# MoodBadgeRev00.net
KiCad netlist of a schematic drawn in EAGLE
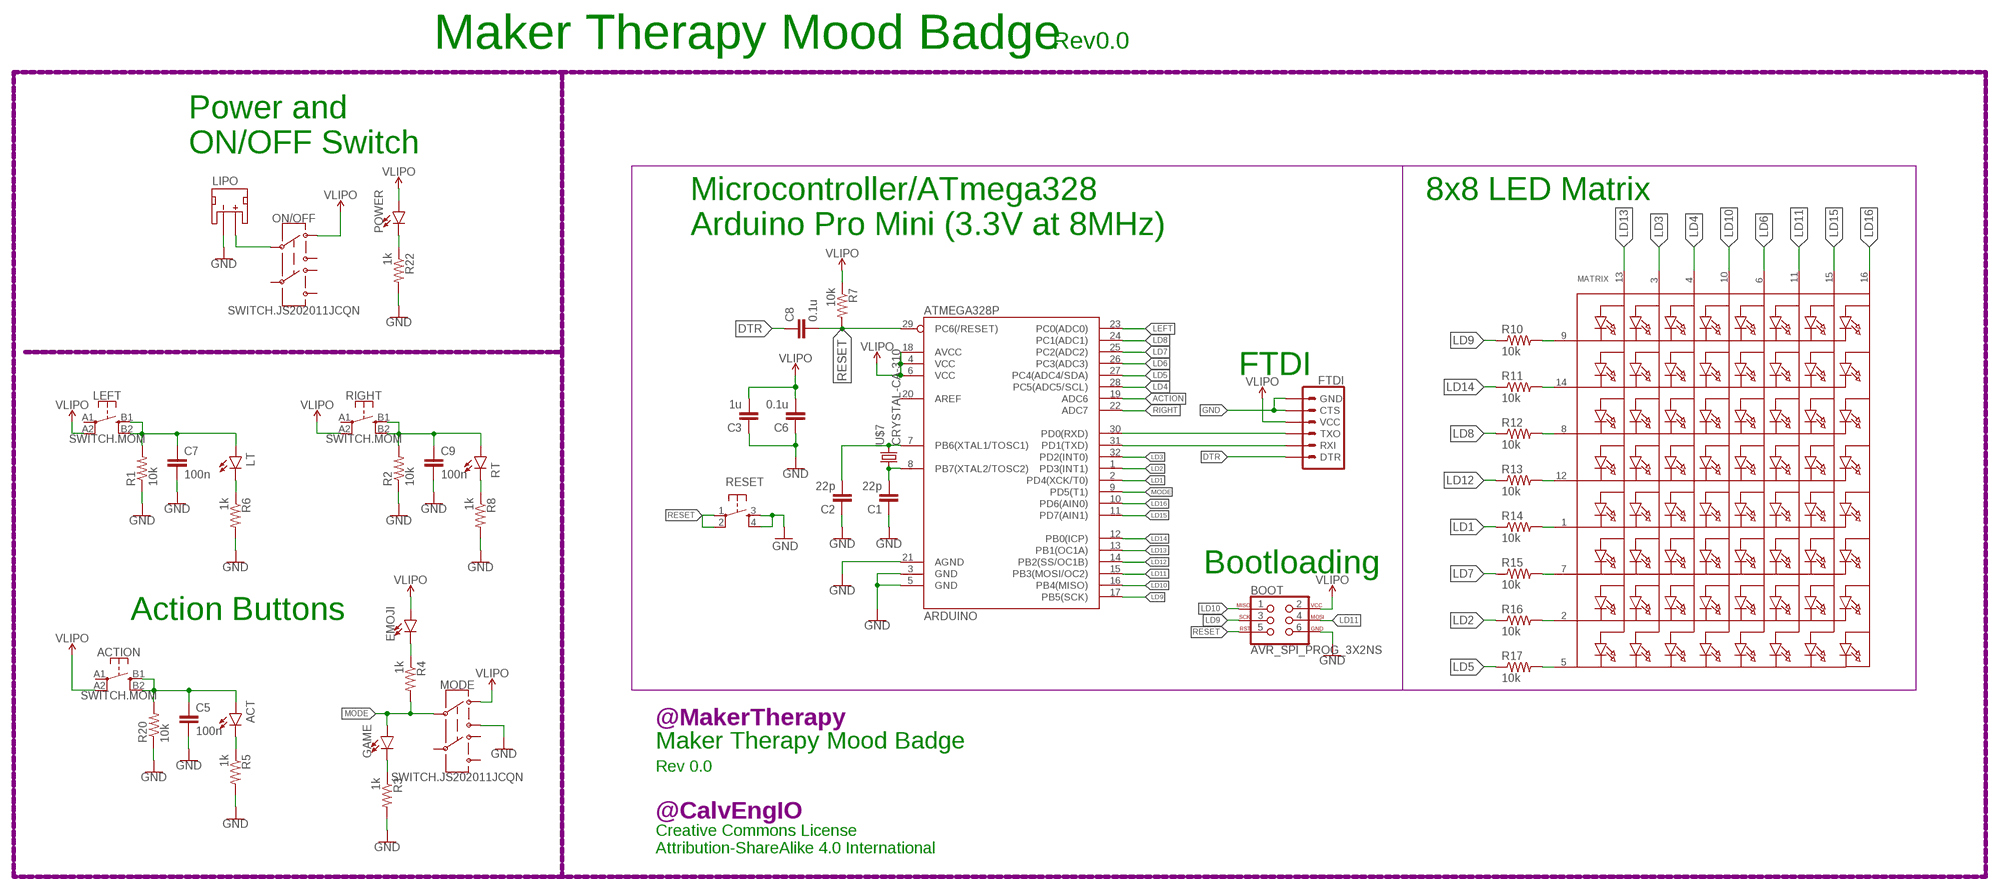
[diagram p0: schematic, sheet 1]

(export (version "E")
  (design (tool "Eeschema 10.0.6"))
  (components
    (comp (ref "ACT")
      (value "LED0603")
      (footprint "eagle-import:LED-0603")
      (libsource (lib "eagle-import") (part "LED0603"))
    )
    (comp (ref "ACTION")
      (value "SWITCH.MOM")
      (footprint "eagle-import:TACTILE_SWITCH_SMD_6.2MM_TALL")
      (libsource (lib "eagle-import") (part "SWITCH.MOM"))
    )
    (comp (ref "ARDUINO")
      (value "ATMEGA328P")
      (footprint "eagle-import:TQFP32-08")
      (libsource (lib "eagle-import") (part "ATMEGA328_SMT-OHMOD"))
    )
    (comp (ref "BOOT")
      (value "AVR_SPI_PROG_3X2NS")
      (footprint "eagle-import:2X3-NS")
      (libsource (lib "eagle-import") (part "AVR_SPI_PROG_3X2NS"))
    )
    (comp (ref "C1")
      (value "22p")
      (footprint "eagle-import:C0402")
      (libsource (lib "eagle-import") (part "CAPACITOR0402"))
    )
    (comp (ref "C2")
      (value "22p")
      (footprint "eagle-import:C0402")
      (libsource (lib "eagle-import") (part "CAPACITOR0402"))
    )
    (comp (ref "C3")
      (value "1u")
      (footprint "eagle-import:C0402")
      (libsource (lib "eagle-import") (part "CAPACITOR0402"))
    )
    (comp (ref "C5")
      (value "100n")
      (footprint "eagle-import:C0402")
      (libsource (lib "eagle-import") (part "CAPACITOR0402"))
    )
    (comp (ref "C6")
      (value "0.1u")
      (footprint "eagle-import:C0402")
      (libsource (lib "eagle-import") (part "CAPACITOR0402"))
    )
    (comp (ref "C7")
      (value "100n")
      (footprint "eagle-import:C0402")
      (libsource (lib "eagle-import") (part "CAPACITOR0402"))
    )
    (comp (ref "C8")
      (value "0.1u")
      (footprint "eagle-import:C0402")
      (libsource (lib "eagle-import") (part "C-EUC0402"))
    )
    (comp (ref "C9")
      (value "100n")
      (footprint "eagle-import:C0402")
      (libsource (lib "eagle-import") (part "CAPACITOR0402"))
    )
    (comp (ref "EMOJI")
      (value "LED0603")
      (footprint "eagle-import:LED-0603")
      (libsource (lib "eagle-import") (part "LED0603"))
    )
    (comp (ref "FTDI")
      (value "6_PIN_SERIAL_TARGETSILK")
      (footprint "eagle-import:6_PIN_SERIAL_TARGET_SIDE_W_SILK")
      (libsource (lib "eagle-import") (part "6_PIN_SERIAL_TARGETSILK"))
    )
    (comp (ref "GAME")
      (value "LED0603")
      (footprint "eagle-import:LED-0603")
      (libsource (lib "eagle-import") (part "LED0603"))
    )
    (comp (ref "LEFT")
      (value "SWITCH.MOM")
      (footprint "eagle-import:TACTILE_SWITCH_SMD_6.2MM_TALL")
      (libsource (lib "eagle-import") (part "SWITCH.MOM"))
    )
    (comp (ref "LIPO")
      (value "JST_2MM_MALE")
      (footprint "eagle-import:JST-2-SMD")
      (libsource (lib "eagle-import") (part "JST_2MM_MALE"))
    )
    (comp (ref "LT")
      (value "LED0603")
      (footprint "eagle-import:LED-0603")
      (libsource (lib "eagle-import") (part "LED0603"))
    )
    (comp (ref "MATRIX")
      (value "SEGMENT_8X8_ROWCATHODEM12A881UR")
      (footprint "eagle-import:SEGMENT_BL-M12A881UR")
      (libsource (lib "eagle-import") (part "SEGMENT_8X8_ROWCATHODEM12A881UR"))
    )
    (comp (ref "MODE")
      (value "SWITCH.JS202011JCQN")
      (footprint "eagle-import:SWITCH.00")
      (libsource (lib "eagle-import") (part "SWITCH.JS202011JCQN"))
    )
    (comp (ref "ON/OFF")
      (value "SWITCH.JS202011JCQN")
      (footprint "eagle-import:SWITCH.00")
      (libsource (lib "eagle-import") (part "SWITCH.JS202011JCQN"))
    )
    (comp (ref "POWER")
      (value "LED5MM")
      (footprint "eagle-import:LED_5MM")
      (libsource (lib "eagle-import") (part "LED5MM"))
    )
    (comp (ref "R1")
      (value "10k")
      (footprint "eagle-import:R0402")
      (libsource (lib "eagle-import") (part "RESISTOR0402"))
    )
    (comp (ref "R2")
      (value "10k")
      (footprint "eagle-import:R0402")
      (libsource (lib "eagle-import") (part "RESISTOR0402"))
    )
    (comp (ref "R3")
      (value "1k")
      (footprint "eagle-import:R0402")
      (libsource (lib "eagle-import") (part "RESISTOR0402"))
    )
    (comp (ref "R4")
      (value "1k")
      (footprint "eagle-import:R0402")
      (libsource (lib "eagle-import") (part "RESISTOR0402"))
    )
    (comp (ref "R5")
      (value "1k")
      (footprint "eagle-import:R0402")
      (libsource (lib "eagle-import") (part "RESISTOR0402"))
    )
    (comp (ref "R6")
      (value "1k")
      (footprint "eagle-import:R0402")
      (libsource (lib "eagle-import") (part "RESISTOR0402"))
    )
    (comp (ref "R7")
      (value "10k")
      (footprint "eagle-import:R0402")
      (libsource (lib "eagle-import") (part "RESISTOR0402"))
    )
    (comp (ref "R8")
      (value "1k")
      (footprint "eagle-import:R0402")
      (libsource (lib "eagle-import") (part "RESISTOR0402"))
    )
    (comp (ref "R10")
      (value "10k")
      (footprint "eagle-import:R0402")
      (libsource (lib "eagle-import") (part "RESISTOR0402"))
    )
    (comp (ref "R11")
      (value "10k")
      (footprint "eagle-import:R0402")
      (libsource (lib "eagle-import") (part "RESISTOR0402"))
    )
    (comp (ref "R12")
      (value "10k")
      (footprint "eagle-import:R0402")
      (libsource (lib "eagle-import") (part "RESISTOR0402"))
    )
    (comp (ref "R13")
      (value "10k")
      (footprint "eagle-import:R0402")
      (libsource (lib "eagle-import") (part "RESISTOR0402"))
    )
    (comp (ref "R14")
      (value "10k")
      (footprint "eagle-import:R0402")
      (libsource (lib "eagle-import") (part "RESISTOR0402"))
    )
    (comp (ref "R15")
      (value "10k")
      (footprint "eagle-import:R0402")
      (libsource (lib "eagle-import") (part "RESISTOR0402"))
    )
    (comp (ref "R16")
      (value "10k")
      (footprint "eagle-import:R0402")
      (libsource (lib "eagle-import") (part "RESISTOR0402"))
    )
    (comp (ref "R17")
      (value "10k")
      (footprint "eagle-import:R0402")
      (libsource (lib "eagle-import") (part "RESISTOR0402"))
    )
    (comp (ref "R20")
      (value "10k")
      (footprint "eagle-import:R0402")
      (libsource (lib "eagle-import") (part "RESISTOR0402"))
    )
    (comp (ref "R22")
      (value "1k")
      (footprint "eagle-import:R0402")
      (libsource (lib "eagle-import") (part "RESISTOR0402"))
    )
    (comp (ref "RESET")
      (value "BUTTON-PTS830GG140")
      (footprint "eagle-import:BUTTON-GULLWING")
      (libsource (lib "eagle-import") (part "BUTTON-PTS830GG140"))
    )
    (comp (ref "RIGHT")
      (value "SWITCH.MOM")
      (footprint "eagle-import:TACTILE_SWITCH_SMD_6.2MM_TALL")
      (libsource (lib "eagle-import") (part "SWITCH.MOM"))
    )
    (comp (ref "RT")
      (value "LED0603")
      (footprint "eagle-import:LED-0603")
      (libsource (lib "eagle-import") (part "LED0603"))
    )
    (comp (ref "U$7")
      (value "CRYSTAL-CA-310")
      (footprint "eagle-import:CA-301")
      (libsource (lib "eagle-import") (part "CRYSTAL-CA-310"))
    )
    (comp (ref "U$8")
      (value "CALVENGIO_HANDLEHANDLE.05")
      (footprint "eagle-import:CALVENGIO_HANDLE.05")
      (libsource (lib "eagle-import") (part "CALVENGIO_HANDLEHANDLE.05"))
    )
    (comp (ref "U$10")
      (value "MAKERTHERAPY.HANDLEMAKERTHERAPY.HANDLE.175")
      (footprint "eagle-import:MAKERTHERAPY.HANDLE.175")
      (libsource (lib "eagle-import") (part "MAKERTHERAPY.HANDLEMAKERTHERAPY.HANDLE.175"))
    )
  )
  (nets
    (net (code "1") (name "ACTION") (class "Default")
      (node (ref "ACT") (pin "A") (pinfunction "A_A") (pintype "passive"))
      (node (ref "ACTION") (pin "B1") (pinfunction "3_B1") (pintype "passive"))
      (node (ref "ACTION") (pin "B2") (pinfunction "4_B2") (pintype "passive"))
      (node (ref "ARDUINO") (pin "19") (pinfunction "ADC6_19") (pintype "bidirectional"))
      (node (ref "C5") (pin "1") (pinfunction "1_1") (pintype "passive"))
      (node (ref "R20") (pin "2") (pinfunction "2_2") (pintype "passive"))
    )
    (net (code "2") (name "DTR") (class "Default")
      (node (ref "C8") (pin "1") (pinfunction "1_1") (pintype "passive"))
      (node (ref "FTDI") (pin "P$1") (pinfunction "DTR_P$1") (pintype "passive"))
    )
    (net (code "3") (name "GND") (class "Default")
      (node (ref "ARDUINO") (pin "21") (pinfunction "AGND_21") (pintype "bidirectional"))
      (node (ref "ARDUINO") (pin "3") (pinfunction "GND_3") (pintype "bidirectional"))
      (node (ref "ARDUINO") (pin "5") (pinfunction "GND_5") (pintype "bidirectional"))
      (node (ref "BOOT") (pin "6") (pinfunction "6_6") (pintype "passive"))
      (node (ref "C1") (pin "1") (pinfunction "1_1") (pintype "passive"))
      (node (ref "C2") (pin "1") (pinfunction "1_1") (pintype "passive"))
      (node (ref "C3") (pin "1") (pinfunction "1_1") (pintype "passive"))
      (node (ref "C5") (pin "2") (pinfunction "2_2") (pintype "passive"))
      (node (ref "C6") (pin "1") (pinfunction "1_1") (pintype "passive"))
      (node (ref "C7") (pin "2") (pinfunction "2_2") (pintype "passive"))
      (node (ref "C9") (pin "2") (pinfunction "2_2") (pintype "passive"))
      (node (ref "FTDI") (pin "P$5") (pinfunction "CTS_P$5") (pintype "passive"))
      (node (ref "FTDI") (pin "P$6") (pinfunction "GND_P$6") (pintype "passive"))
      (node (ref "LIPO") (pin "1") (pinfunction "-_1") (pintype "bidirectional"))
      (node (ref "MODE") (pin "3") (pinfunction "3_3") (pintype "bidirectional"))
      (node (ref "R1") (pin "1") (pinfunction "1_1") (pintype "passive"))
      (node (ref "R2") (pin "1") (pinfunction "1_1") (pintype "passive"))
      (node (ref "R20") (pin "1") (pinfunction "1_1") (pintype "passive"))
      (node (ref "R22") (pin "2") (pinfunction "2_2") (pintype "passive"))
      (node (ref "R3") (pin "2") (pinfunction "2_2") (pintype "passive"))
      (node (ref "R5") (pin "2") (pinfunction "2_2") (pintype "passive"))
      (node (ref "R6") (pin "2") (pinfunction "2_2") (pintype "passive"))
      (node (ref "R8") (pin "2") (pinfunction "2_2") (pintype "passive"))
      (node (ref "RESET") (pin "3") (pinfunction "3_3") (pintype "passive"))
      (node (ref "RESET") (pin "4") (pinfunction "4_4") (pintype "passive"))
    )
    (net (code "4") (name "LD1") (class "Default")
      (node (ref "ARDUINO") (pin "2") (pinfunction "PD4(XCK/T0)_2") (pintype "bidirectional"))
      (node (ref "R14") (pin "1") (pinfunction "1_1") (pintype "passive"))
    )
    (net (code "5") (name "LD2") (class "Default")
      (node (ref "ARDUINO") (pin "1") (pinfunction "PD3(INT1)_1") (pintype "bidirectional"))
      (node (ref "R16") (pin "1") (pinfunction "1_1") (pintype "passive"))
    )
    (net (code "6") (name "LD3") (class "Default")
      (node (ref "ARDUINO") (pin "32") (pinfunction "PD2(INT0)_32") (pintype "bidirectional"))
      (node (ref "MATRIX") (pin "3") (pinfunction "A2_3") (pintype "bidirectional"))
    )
    (net (code "7") (name "LD4") (class "Default")
      (node (ref "ARDUINO") (pin "28") (pinfunction "PC5(ADC5/SCL)_28") (pintype "bidirectional"))
      (node (ref "MATRIX") (pin "4") (pinfunction "A3_4") (pintype "bidirectional"))
    )
    (net (code "8") (name "LD5") (class "Default")
      (node (ref "ARDUINO") (pin "27") (pinfunction "PC4(ADC4/SDA)_27") (pintype "bidirectional"))
      (node (ref "R17") (pin "1") (pinfunction "1_1") (pintype "passive"))
    )
    (net (code "9") (name "LD6") (class "Default")
      (node (ref "ARDUINO") (pin "26") (pinfunction "PC3(ADC3)_26") (pintype "bidirectional"))
      (node (ref "MATRIX") (pin "6") (pinfunction "A5_6") (pintype "bidirectional"))
    )
    (net (code "10") (name "LD7") (class "Default")
      (node (ref "ARDUINO") (pin "25") (pinfunction "PC2(ADC2)_25") (pintype "bidirectional"))
      (node (ref "R15") (pin "1") (pinfunction "1_1") (pintype "passive"))
    )
    (net (code "11") (name "LD8") (class "Default")
      (node (ref "ARDUINO") (pin "24") (pinfunction "PC1(ADC1)_24") (pintype "bidirectional"))
      (node (ref "R12") (pin "1") (pinfunction "1_1") (pintype "passive"))
    )
    (net (code "12") (name "LD9") (class "Default")
      (node (ref "ARDUINO") (pin "17") (pinfunction "PB5(SCK)_17") (pintype "bidirectional"))
      (node (ref "BOOT") (pin "3") (pinfunction "3_3") (pintype "passive"))
      (node (ref "R10") (pin "1") (pinfunction "1_1") (pintype "passive"))
    )
    (net (code "13") (name "LD10") (class "Default")
      (node (ref "ARDUINO") (pin "16") (pinfunction "PB4(MISO)_16") (pintype "bidirectional"))
      (node (ref "BOOT") (pin "1") (pinfunction "1_1") (pintype "passive"))
      (node (ref "MATRIX") (pin "10") (pinfunction "A4_10") (pintype "bidirectional"))
    )
    (net (code "14") (name "LD11") (class "Default")
      (node (ref "ARDUINO") (pin "15") (pinfunction "PB3(MOSI/OC2)_15") (pintype "bidirectional"))
      (node (ref "BOOT") (pin "4") (pinfunction "4_4") (pintype "passive"))
      (node (ref "MATRIX") (pin "11") (pinfunction "A6_11") (pintype "bidirectional"))
    )
    (net (code "15") (name "LD12") (class "Default")
      (node (ref "ARDUINO") (pin "14") (pinfunction "PB2(SS/OC1B)_14") (pintype "bidirectional"))
      (node (ref "R13") (pin "1") (pinfunction "1_1") (pintype "passive"))
    )
    (net (code "16") (name "LD13") (class "Default")
      (node (ref "ARDUINO") (pin "13") (pinfunction "PB1(OC1A)_13") (pintype "bidirectional"))
      (node (ref "MATRIX") (pin "13") (pinfunction "A1_13") (pintype "bidirectional"))
    )
    (net (code "17") (name "LD14") (class "Default")
      (node (ref "ARDUINO") (pin "12") (pinfunction "PB0(ICP)_12") (pintype "bidirectional"))
      (node (ref "R11") (pin "1") (pinfunction "1_1") (pintype "passive"))
    )
    (net (code "18") (name "LD15") (class "Default")
      (node (ref "ARDUINO") (pin "11") (pinfunction "PD7(AIN1)_11") (pintype "bidirectional"))
      (node (ref "MATRIX") (pin "15") (pinfunction "A7_15") (pintype "bidirectional"))
    )
    (net (code "19") (name "LD16") (class "Default")
      (node (ref "ARDUINO") (pin "10") (pinfunction "PD6(AIN0)_10") (pintype "bidirectional"))
      (node (ref "MATRIX") (pin "16") (pinfunction "A8_16") (pintype "bidirectional"))
    )
    (net (code "20") (name "LEFT") (class "Default")
      (node (ref "ARDUINO") (pin "23") (pinfunction "PC0(ADC0)_23") (pintype "bidirectional"))
      (node (ref "C7") (pin "1") (pinfunction "1_1") (pintype "passive"))
      (node (ref "LEFT") (pin "B1") (pinfunction "3_B1") (pintype "passive"))
      (node (ref "LEFT") (pin "B2") (pinfunction "4_B2") (pintype "passive"))
      (node (ref "LT") (pin "A") (pinfunction "A_A") (pintype "passive"))
      (node (ref "R1") (pin "2") (pinfunction "2_2") (pintype "passive"))
    )
    (net (code "21") (name "MODE") (class "Default")
      (node (ref "ARDUINO") (pin "9") (pinfunction "PD5(T1)_9") (pintype "bidirectional"))
      (node (ref "GAME") (pin "A") (pinfunction "A_A") (pintype "passive"))
      (node (ref "MODE") (pin "2") (pinfunction "2_2") (pintype "bidirectional"))
      (node (ref "R4") (pin "2") (pinfunction "2_2") (pintype "passive"))
    )
    (net (code "22") (name "Net-(ACT-PadC)") (class "Default")
      (node (ref "ACT") (pin "C") (pinfunction "C_C") (pintype "passive"))
      (node (ref "R5") (pin "1") (pinfunction "1_1") (pintype "passive"))
    )
    (net (code "23") (name "Net-(ARDUINO-PB6(XTAL1{slash}TOSC1))") (class "Default")
      (node (ref "ARDUINO") (pin "7") (pinfunction "PB6(XTAL1/TOSC1)_7") (pintype "bidirectional"))
      (node (ref "C2") (pin "2") (pinfunction "2_2") (pintype "passive"))
      (node (ref "U$7") (pin "2") (pinfunction "2_2") (pintype "passive"))
    )
    (net (code "24") (name "Net-(ARDUINO-PB7(XTAL2{slash}TOSC2))") (class "Default")
      (node (ref "ARDUINO") (pin "8") (pinfunction "PB7(XTAL2/TOSC2)_8") (pintype "bidirectional"))
      (node (ref "C1") (pin "2") (pinfunction "2_2") (pintype "passive"))
      (node (ref "U$7") (pin "1") (pinfunction "1_1") (pintype "passive"))
    )
    (net (code "25") (name "Net-(ARDUINO-PD0(RXD))") (class "Default")
      (node (ref "ARDUINO") (pin "30") (pinfunction "PD0(RXD)_30") (pintype "bidirectional"))
      (node (ref "FTDI") (pin "P$2") (pinfunction "TXO_P$2") (pintype "passive"))
    )
    (net (code "26") (name "Net-(ARDUINO-PD1(TXD))") (class "Default")
      (node (ref "ARDUINO") (pin "31") (pinfunction "PD1(TXD)_31") (pintype "bidirectional"))
      (node (ref "FTDI") (pin "P$3") (pinfunction "RXI_P$3") (pintype "passive"))
    )
    (net (code "27") (name "Net-(EMOJI-PadC)") (class "Default")
      (node (ref "EMOJI") (pin "C") (pinfunction "C_C") (pintype "passive"))
      (node (ref "R4") (pin "1") (pinfunction "1_1") (pintype "passive"))
    )
    (net (code "28") (name "Net-(GAME-PadC)") (class "Default")
      (node (ref "GAME") (pin "C") (pinfunction "C_C") (pintype "passive"))
      (node (ref "R3") (pin "1") (pinfunction "1_1") (pintype "passive"))
    )
    (net (code "29") (name "Net-(LIPO-+)") (class "Default")
      (node (ref "LIPO") (pin "2") (pinfunction "+_2") (pintype "bidirectional"))
      (node (ref "ON/OFF") (pin "2") (pinfunction "2_2") (pintype "bidirectional"))
    )
    (net (code "30") (name "Net-(LT-PadC)") (class "Default")
      (node (ref "LT") (pin "C") (pinfunction "C_C") (pintype "passive"))
      (node (ref "R6") (pin "1") (pinfunction "1_1") (pintype "passive"))
    )
    (net (code "31") (name "Net-(MATRIX-K1)") (class "Default")
      (node (ref "MATRIX") (pin "9") (pinfunction "K1_9") (pintype "bidirectional"))
      (node (ref "R10") (pin "2") (pinfunction "2_2") (pintype "passive"))
    )
    (net (code "32") (name "Net-(MATRIX-K2)") (class "Default")
      (node (ref "MATRIX") (pin "14") (pinfunction "K2_14") (pintype "bidirectional"))
      (node (ref "R11") (pin "2") (pinfunction "2_2") (pintype "passive"))
    )
    (net (code "33") (name "Net-(MATRIX-K3)") (class "Default")
      (node (ref "MATRIX") (pin "8") (pinfunction "K3_8") (pintype "bidirectional"))
      (node (ref "R12") (pin "2") (pinfunction "2_2") (pintype "passive"))
    )
    (net (code "34") (name "Net-(MATRIX-K4)") (class "Default")
      (node (ref "MATRIX") (pin "12") (pinfunction "K4_12") (pintype "bidirectional"))
      (node (ref "R13") (pin "2") (pinfunction "2_2") (pintype "passive"))
    )
    (net (code "35") (name "Net-(MATRIX-K5)") (class "Default")
      (node (ref "MATRIX") (pin "1") (pinfunction "K5_1") (pintype "bidirectional"))
      (node (ref "R14") (pin "2") (pinfunction "2_2") (pintype "passive"))
    )
    (net (code "36") (name "Net-(MATRIX-K6)") (class "Default")
      (node (ref "MATRIX") (pin "7") (pinfunction "K6_7") (pintype "bidirectional"))
      (node (ref "R15") (pin "2") (pinfunction "2_2") (pintype "passive"))
    )
    (net (code "37") (name "Net-(MATRIX-K7)") (class "Default")
      (node (ref "MATRIX") (pin "2") (pinfunction "K7_2") (pintype "bidirectional"))
      (node (ref "R16") (pin "2") (pinfunction "2_2") (pintype "passive"))
    )
    (net (code "38") (name "Net-(MATRIX-K8)") (class "Default")
      (node (ref "MATRIX") (pin "5") (pinfunction "K8_5") (pintype "bidirectional"))
      (node (ref "R17") (pin "2") (pinfunction "2_2") (pintype "passive"))
    )
    (net (code "39") (name "Net-(POWER-C)") (class "Default")
      (node (ref "POWER") (pin "K") (pinfunction "C_K") (pintype "passive"))
      (node (ref "R22") (pin "1") (pinfunction "1_1") (pintype "passive"))
    )
    (net (code "40") (name "Net-(R8-Pad1)") (class "Default")
      (node (ref "R8") (pin "1") (pinfunction "1_1") (pintype "passive"))
      (node (ref "RT") (pin "C") (pinfunction "C_C") (pintype "passive"))
    )
    (net (code "41") (name "RESET") (class "Default")
      (node (ref "ARDUINO") (pin "29") (pinfunction "PC6(/RESET)_29") (pintype "bidirectional"))
      (node (ref "BOOT") (pin "5") (pinfunction "5_5") (pintype "passive"))
      (node (ref "C8") (pin "2") (pinfunction "2_2") (pintype "passive"))
      (node (ref "R7") (pin "2") (pinfunction "2_2") (pintype "passive"))
      (node (ref "RESET") (pin "1") (pinfunction "1_1") (pintype "passive"))
      (node (ref "RESET") (pin "2") (pinfunction "2_2") (pintype "passive"))
    )
    (net (code "42") (name "RIGHT") (class "Default")
      (node (ref "ARDUINO") (pin "22") (pinfunction "ADC7_22") (pintype "bidirectional"))
      (node (ref "C9") (pin "1") (pinfunction "1_1") (pintype "passive"))
      (node (ref "R2") (pin "2") (pinfunction "2_2") (pintype "passive"))
      (node (ref "RIGHT") (pin "B1") (pinfunction "3_B1") (pintype "passive"))
      (node (ref "RIGHT") (pin "B2") (pinfunction "4_B2") (pintype "passive"))
      (node (ref "RT") (pin "A") (pinfunction "A_A") (pintype "passive"))
    )
    (net (code "43") (name "VLIPO") (class "Default")
      (node (ref "ACTION") (pin "A2") (pinfunction "2_A2") (pintype "passive"))
      (node (ref "ARDUINO") (pin "18") (pinfunction "AVCC_18") (pintype "bidirectional"))
      (node (ref "ARDUINO") (pin "4") (pinfunction "VCC_4") (pintype "bidirectional"))
      (node (ref "ARDUINO") (pin "6") (pinfunction "VCC_6") (pintype "bidirectional"))
      (node (ref "BOOT") (pin "2") (pinfunction "2_2") (pintype "passive"))
      (node (ref "C3") (pin "2") (pinfunction "2_2") (pintype "passive"))
      (node (ref "C6") (pin "2") (pinfunction "2_2") (pintype "passive"))
      (node (ref "EMOJI") (pin "A") (pinfunction "A_A") (pintype "passive"))
      (node (ref "FTDI") (pin "P$4") (pinfunction "VCC_P$4") (pintype "passive"))
      (node (ref "LEFT") (pin "A2") (pinfunction "2_A2") (pintype "passive"))
      (node (ref "MODE") (pin "1") (pinfunction "1_1") (pintype "bidirectional"))
      (node (ref "ON/OFF") (pin "1") (pinfunction "1_1") (pintype "bidirectional"))
      (node (ref "POWER") (pin "A") (pinfunction "A_A") (pintype "passive"))
      (node (ref "R7") (pin "1") (pinfunction "1_1") (pintype "passive"))
      (node (ref "RIGHT") (pin "A2") (pinfunction "2_A2") (pintype "passive"))
    )
    (net (code "44") (name "unconnected-(ACTION-1-PadA1)") (class "Default")
      (node (ref "ACTION") (pin "A1") (pinfunction "1_A1") (pintype "passive"))
    )
    (net (code "45") (name "unconnected-(ARDUINO-AREF-Pad20)") (class "Default")
      (node (ref "ARDUINO") (pin "20") (pinfunction "AREF_20") (pintype "bidirectional"))
    )
    (net (code "46") (name "unconnected-(LEFT-1-PadA1)") (class "Default")
      (node (ref "LEFT") (pin "A1") (pinfunction "1_A1") (pintype "passive"))
    )
    (net (code "47") (name "unconnected-(LIPO-PAD1-PadNC1)") (class "Default")
      (node (ref "LIPO") (pin "NC1") (pinfunction "PAD1_NC1") (pintype "bidirectional"))
    )
    (net (code "48") (name "unconnected-(LIPO-PAD2-PadNC2)") (class "Default")
      (node (ref "LIPO") (pin "NC2") (pinfunction "PAD2_NC2") (pintype "bidirectional"))
    )
    (net (code "49") (name "unconnected-(MODE-Pad5)") (class "Default")
      (node (ref "MODE") (pin "5") (pinfunction "5_5") (pintype "bidirectional"))
    )
    (net (code "50") (name "unconnected-(MODE-Pad6)") (class "Default")
      (node (ref "MODE") (pin "6") (pinfunction "6_6") (pintype "bidirectional"))
    )
    (net (code "51") (name "unconnected-(MODE-Pad7)") (class "Default")
      (node (ref "MODE") (pin "7") (pinfunction "7_7") (pintype "bidirectional"))
    )
    (net (code "52") (name "unconnected-(ON/OFF-Pad3)") (class "Default")
      (node (ref "ON/OFF") (pin "3") (pinfunction "3_3") (pintype "bidirectional"))
    )
    (net (code "53") (name "unconnected-(ON/OFF-Pad5)") (class "Default")
      (node (ref "ON/OFF") (pin "5") (pinfunction "5_5") (pintype "bidirectional"))
    )
    (net (code "54") (name "unconnected-(ON/OFF-Pad6)") (class "Default")
      (node (ref "ON/OFF") (pin "6") (pinfunction "6_6") (pintype "bidirectional"))
    )
    (net (code "55") (name "unconnected-(ON/OFF-Pad7)") (class "Default")
      (node (ref "ON/OFF") (pin "7") (pinfunction "7_7") (pintype "bidirectional"))
    )
    (net (code "56") (name "unconnected-(RIGHT-1-PadA1)") (class "Default")
      (node (ref "RIGHT") (pin "A1") (pinfunction "1_A1") (pintype "passive"))
    )
  )
)
